# akabeacon_square.net
KiCad netlist of a schematic drawn in EAGLE
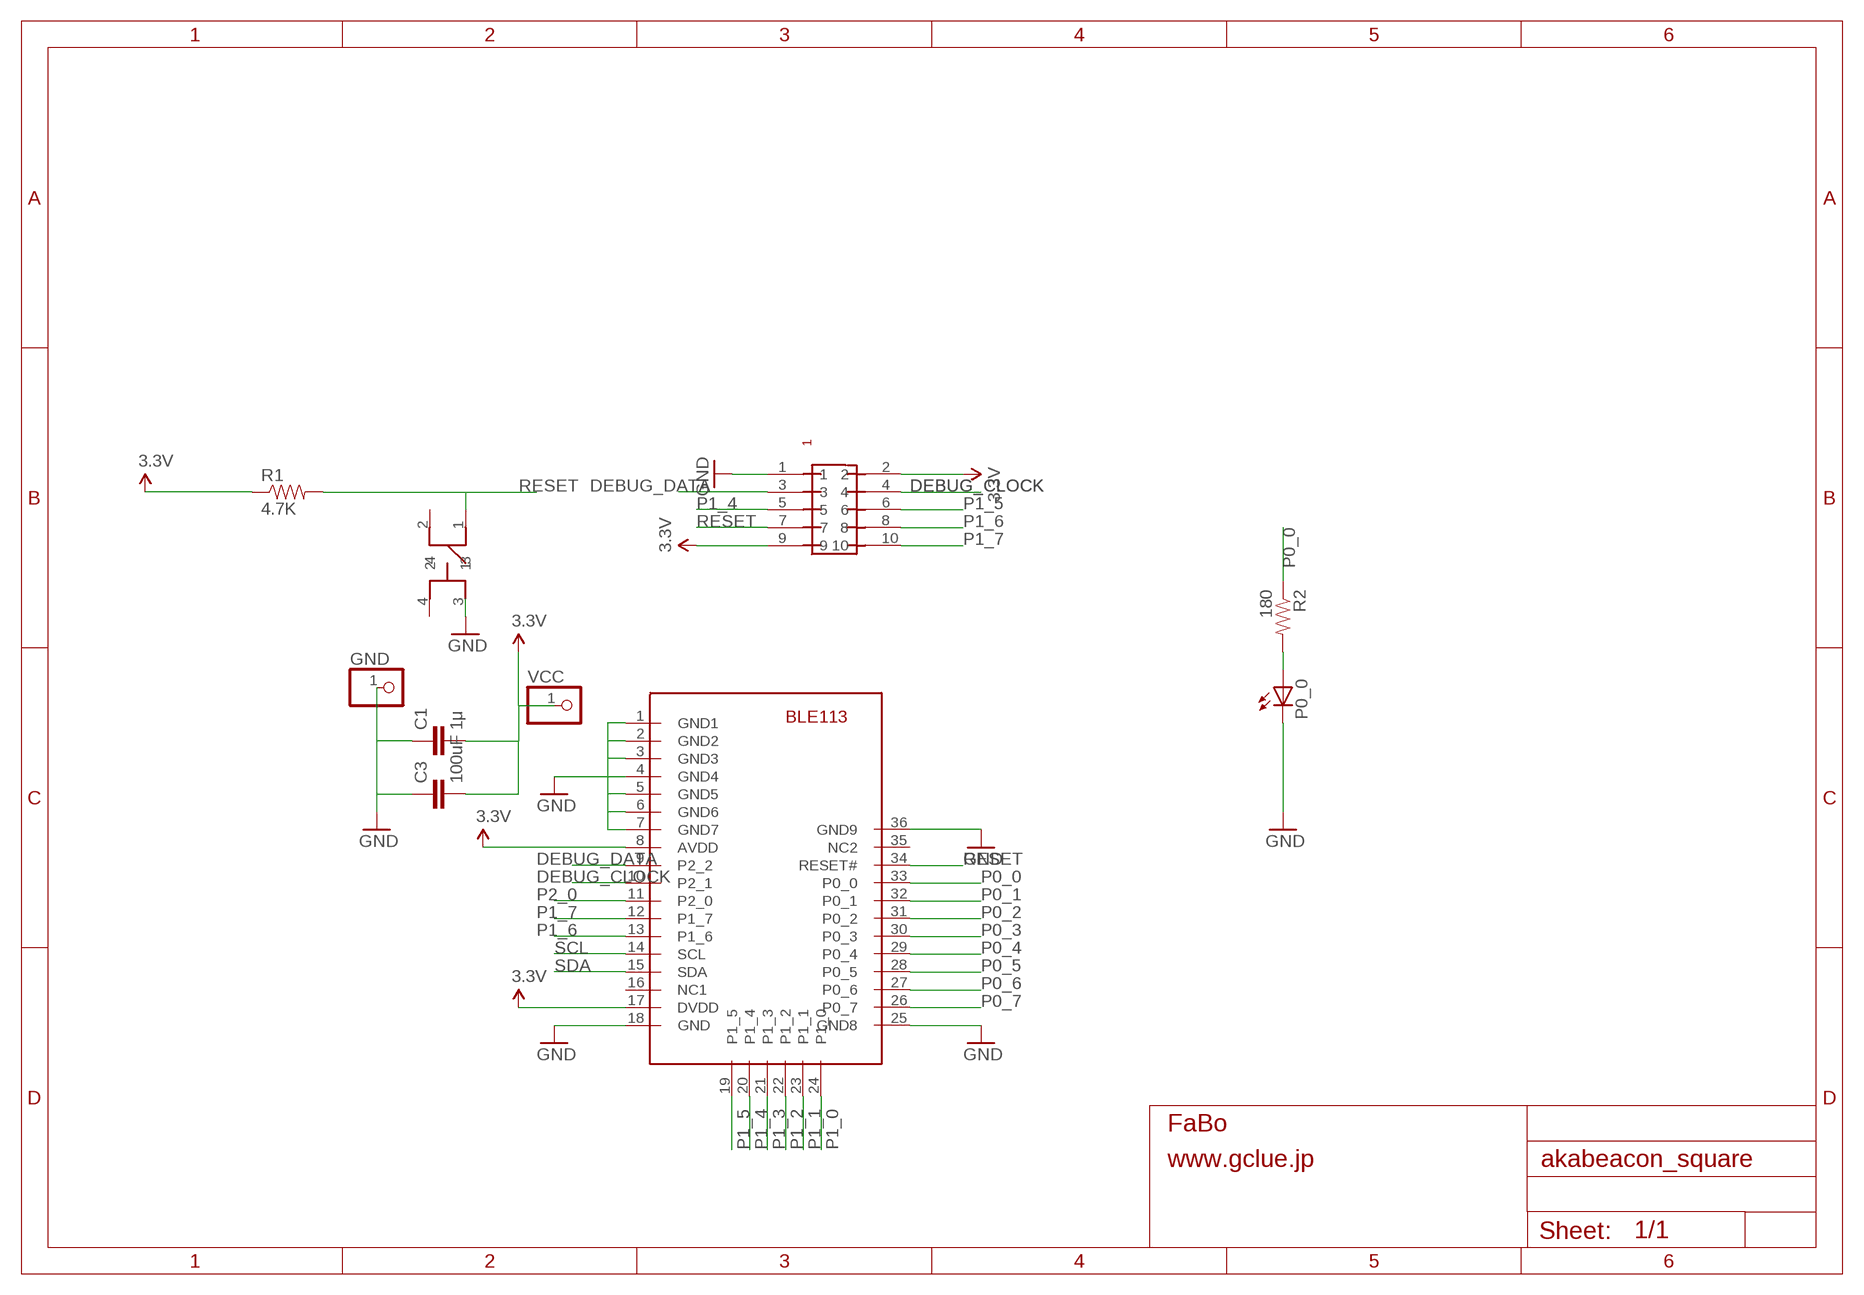
[diagram p0: schematic, sheet 1]

(export (version "E")
  (design (tool "Eeschema 10.0.6"))
  (components
    (comp (ref "C1")
      (value "1μ")
      (footprint "eagle-import:0603-CAP")
      (libsource (lib "eagle-import") (part "CAP0603-CAP"))
    )
    (comp (ref "C3")
      (value "100uF")
      (footprint "eagle-import:1206")
      (libsource (lib "eagle-import") (part "10UF-6.3V-20%(1206)"))
    )
    (comp (ref "GND")
      (value "PINHD-1X1CB")
      (footprint "eagle-import:1X01-CLEANBIG")
      (libsource (lib "eagle-import") (part "PINHD-1X1CB"))
    )
    (comp (ref "P0_0")
      (value "LEDCHIP-LED0603")
      (footprint "eagle-import:CHIP-LED0603")
      (libsource (lib "eagle-import") (part "LEDCHIP-LED0603"))
    )
    (comp (ref "R1")
      (value "4.7K")
      (footprint "eagle-import:0603-RES")
      (libsource (lib "eagle-import") (part "RESISTOR0603-RES"))
    )
    (comp (ref "R2")
      (value "180")
      (footprint "eagle-import:0603-RES")
      (libsource (lib "eagle-import") (part "RESISTOR0603-RES"))
    )
    (comp (ref "U$2")
      (value "PIN-HEADER-SMT(1.27MM)2X5")
      (footprint "eagle-import:PIN-HEADER-SMT(1.27MM)2X5")
      (libsource (lib "eagle-import") (part "PIN-HEADER-SMT(1.27MM)2X5"))
    )
    (comp (ref "U$5")
      (value "BLE113")
      (footprint "eagle-import:BLE113")
      (libsource (lib "eagle-import") (part "BLE113"))
    )
    (comp (ref "U$8")
      (value "SWITCH-LS6J2M-T")
      (footprint "eagle-import:SWICTH-LS6J2M-T")
      (libsource (lib "eagle-import") (part "SWITCH-LS6J2M-T"))
    )
    (comp (ref "VCC")
      (value "PINHD-1X1CB")
      (footprint "eagle-import:1X01-CLEANBIG")
      (libsource (lib "eagle-import") (part "PINHD-1X1CB"))
    )
  )
  (nets
    (net (code "1") (name "/DEBUG_CLOCK") (class "Default")
      (node (ref "U$2") (pin "4") (pinfunction "4_4") (pintype "bidirectional"))
      (node (ref "U$5") (pin "10") (pinfunction "P2_1_10") (pintype "bidirectional"))
    )
    (net (code "2") (name "/DEBUG_DATA") (class "Default")
      (node (ref "U$2") (pin "3") (pinfunction "3_3") (pintype "bidirectional"))
      (node (ref "U$5") (pin "9") (pinfunction "P2_2_9") (pintype "bidirectional"))
    )
    (net (code "3") (name "/P0_0") (class "Default")
      (node (ref "R2") (pin "1") (pinfunction "1_1") (pintype "passive"))
      (node (ref "U$5") (pin "33") (pinfunction "P0_0_33") (pintype "bidirectional"))
    )
    (net (code "4") (name "/P0_1") (class "Default")
      (node (ref "U$5") (pin "32") (pinfunction "P0_1_32") (pintype "bidirectional"))
    )
    (net (code "5") (name "/P0_2") (class "Default")
      (node (ref "U$5") (pin "31") (pinfunction "P0_2_31") (pintype "bidirectional"))
    )
    (net (code "6") (name "/P0_3") (class "Default")
      (node (ref "U$5") (pin "30") (pinfunction "P0_3_30") (pintype "bidirectional"))
    )
    (net (code "7") (name "/P0_4") (class "Default")
      (node (ref "U$5") (pin "29") (pinfunction "P0_4_29") (pintype "bidirectional"))
    )
    (net (code "8") (name "/P0_5") (class "Default")
      (node (ref "U$5") (pin "28") (pinfunction "P0_5_28") (pintype "bidirectional"))
    )
    (net (code "9") (name "/P0_6") (class "Default")
      (node (ref "U$5") (pin "27") (pinfunction "P0_6_27") (pintype "bidirectional"))
    )
    (net (code "10") (name "/P0_7") (class "Default")
      (node (ref "U$5") (pin "26") (pinfunction "P0_7_26") (pintype "bidirectional"))
    )
    (net (code "11") (name "/P1_0") (class "Default")
      (node (ref "U$5") (pin "24") (pinfunction "P1_0_24") (pintype "bidirectional"))
    )
    (net (code "12") (name "/P1_1") (class "Default")
      (node (ref "U$5") (pin "23") (pinfunction "P1_1_23") (pintype "bidirectional"))
    )
    (net (code "13") (name "/P1_2") (class "Default")
      (node (ref "U$5") (pin "22") (pinfunction "P1_2_22") (pintype "bidirectional"))
    )
    (net (code "14") (name "/P1_3") (class "Default")
      (node (ref "U$5") (pin "21") (pinfunction "P1_3_21") (pintype "bidirectional"))
    )
    (net (code "15") (name "/P1_4") (class "Default")
      (node (ref "U$2") (pin "5") (pinfunction "5_5") (pintype "bidirectional"))
      (node (ref "U$5") (pin "20") (pinfunction "P1_4_20") (pintype "bidirectional"))
    )
    (net (code "16") (name "/P1_5") (class "Default")
      (node (ref "U$2") (pin "6") (pinfunction "6_6") (pintype "bidirectional"))
      (node (ref "U$5") (pin "19") (pinfunction "P1_5_19") (pintype "bidirectional"))
    )
    (net (code "17") (name "/P1_6") (class "Default")
      (node (ref "U$2") (pin "8") (pinfunction "8_8") (pintype "bidirectional"))
      (node (ref "U$5") (pin "13") (pinfunction "P1_6_13") (pintype "bidirectional"))
    )
    (net (code "18") (name "/P1_7") (class "Default")
      (node (ref "U$2") (pin "10") (pinfunction "10_10") (pintype "bidirectional"))
      (node (ref "U$5") (pin "12") (pinfunction "P1_7_12") (pintype "bidirectional"))
    )
    (net (code "19") (name "/P2_0") (class "Default")
      (node (ref "U$5") (pin "11") (pinfunction "P2_0_11") (pintype "bidirectional"))
    )
    (net (code "20") (name "/RESET") (class "Default")
      (node (ref "R1") (pin "2") (pinfunction "2_2") (pintype "passive"))
      (node (ref "U$2") (pin "7") (pinfunction "7_7") (pintype "bidirectional"))
      (node (ref "U$5") (pin "34") (pinfunction "RESET#_34") (pintype "bidirectional"))
      (node (ref "U$8") (pin "1") (pinfunction "1_1") (pintype "bidirectional"))
    )
    (net (code "21") (name "/SCL") (class "Default")
      (node (ref "U$5") (pin "14") (pinfunction "SCL_14") (pintype "bidirectional"))
    )
    (net (code "22") (name "/SDA") (class "Default")
      (node (ref "U$5") (pin "15") (pinfunction "SDA_15") (pintype "bidirectional"))
    )
    (net (code "23") (name "3.3V") (class "Default")
      (node (ref "C1") (pin "2") (pinfunction "2_2") (pintype "passive"))
      (node (ref "C3") (pin "2") (pinfunction "2_2") (pintype "passive"))
      (node (ref "R1") (pin "1") (pinfunction "1_1") (pintype "passive"))
      (node (ref "U$2") (pin "2") (pinfunction "2_2") (pintype "bidirectional"))
      (node (ref "U$2") (pin "9") (pinfunction "9_9") (pintype "bidirectional"))
      (node (ref "U$5") (pin "17") (pinfunction "DVDD_17") (pintype "bidirectional"))
      (node (ref "U$5") (pin "8") (pinfunction "AVDD_8") (pintype "bidirectional"))
      (node (ref "VCC") (pin "1") (pinfunction "1_1") (pintype "passive"))
    )
    (net (code "24") (name "GND") (class "Default")
      (node (ref "C1") (pin "1") (pinfunction "1_1") (pintype "passive"))
      (node (ref "C3") (pin "1") (pinfunction "1_1") (pintype "passive"))
      (node (ref "GND") (pin "1") (pinfunction "1_1") (pintype "passive"))
      (node (ref "P0_0") (pin "C") (pinfunction "C_C") (pintype "passive"))
      (node (ref "U$2") (pin "1") (pinfunction "1_1") (pintype "bidirectional"))
      (node (ref "U$5") (pin "1") (pinfunction "GND1_1") (pintype "bidirectional"))
      (node (ref "U$5") (pin "18") (pinfunction "GND_18") (pintype "bidirectional"))
      (node (ref "U$5") (pin "2") (pinfunction "GND2_2") (pintype "bidirectional"))
      (node (ref "U$5") (pin "25") (pinfunction "GND8_25") (pintype "bidirectional"))
      (node (ref "U$5") (pin "3") (pinfunction "GND3_3") (pintype "bidirectional"))
      (node (ref "U$5") (pin "36") (pinfunction "GND9_36") (pintype "bidirectional"))
      (node (ref "U$5") (pin "4") (pinfunction "GND4_4") (pintype "bidirectional"))
      (node (ref "U$5") (pin "5") (pinfunction "GND5_5") (pintype "bidirectional"))
      (node (ref "U$5") (pin "6") (pinfunction "GND6_6") (pintype "bidirectional"))
      (node (ref "U$5") (pin "7") (pinfunction "GND7_7") (pintype "bidirectional"))
      (node (ref "U$8") (pin "3") (pinfunction "3_3") (pintype "bidirectional"))
    )
    (net (code "25") (name "Net-(P0_0-PadA)") (class "Default")
      (node (ref "P0_0") (pin "A") (pinfunction "A_A") (pintype "passive"))
      (node (ref "R2") (pin "2") (pinfunction "2_2") (pintype "passive"))
    )
    (net (code "26") (name "unconnected-(U$5-NC1-Pad16)") (class "Default")
      (node (ref "U$5") (pin "16") (pinfunction "NC1_16") (pintype "bidirectional"))
    )
    (net (code "27") (name "unconnected-(U$5-NC2-Pad35)") (class "Default")
      (node (ref "U$5") (pin "35") (pinfunction "NC2_35") (pintype "bidirectional"))
    )
    (net (code "28") (name "unconnected-(U$8-Pad2)") (class "Default")
      (node (ref "U$8") (pin "2") (pinfunction "2_2") (pintype "bidirectional"))
    )
    (net (code "29") (name "unconnected-(U$8-Pad4)") (class "Default")
      (node (ref "U$8") (pin "4") (pinfunction "4_4") (pintype "bidirectional"))
    )
  )
)
